# mcp23s17_sample.net
KiCad netlist of a schematic drawn in EAGLE
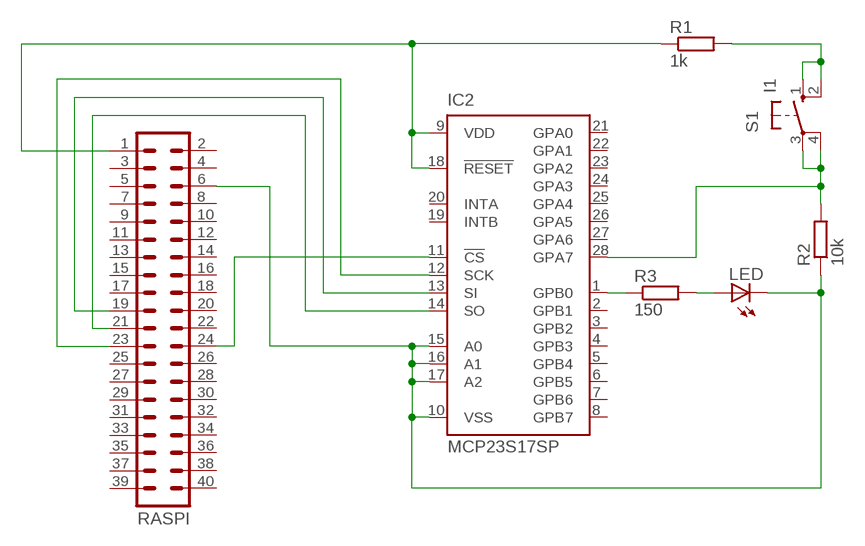
[diagram p0: schematic, sheet 1]

(export (version "E")
  (design (tool "Eeschema 10.0.6"))
  (components
    (comp (ref "IC2")
      (value "MCP23S17SP")
      (footprint "eagle-import:DIL28-3")
      (fields (field (name "MF") "MICROCHIP") (field (name "MPN") "MCP23S17-E/SP"))
      (libsource (lib "eagle-import") (part "MCP23S17SP"))
    )
    (comp (ref "LED")
      (value "LED5MM")
      (footprint "eagle-import:LED5MM")
      (libsource (lib "eagle-import") (part "LED5MM"))
    )
    (comp (ref "R1")
      (value "1k")
      (footprint "eagle-import:0207_10")
      (libsource (lib "eagle-import") (part "R-EU_0207/10"))
    )
    (comp (ref "R2")
      (value "10k")
      (footprint "eagle-import:0207_10")
      (libsource (lib "eagle-import") (part "R-EU_0207/10"))
    )
    (comp (ref "R3")
      (value "150")
      (footprint "eagle-import:0207_10")
      (libsource (lib "eagle-import") (part "R-EU_0207/10"))
    )
    (comp (ref "RASPI")
      (value "ML40")
      (footprint "eagle-import:ML40")
      (libsource (lib "eagle-import") (part "ML40"))
    )
    (comp (ref "S1")
      (value "I1")
      (footprint "eagle-import:B3F-10XX")
      (fields (field (name "MPN") "B3F-1000"))
      (libsource (lib "eagle-import") (part "10-XX"))
    )
  )
  (nets
    (net (code "1") (name "Net-(IC2-A0)") (class "Default")
      (node (ref "IC2") (pin "10") (pinfunction "VSS_10") (pintype "power_in"))
      (node (ref "IC2") (pin "15") (pinfunction "A0_15") (pintype "input"))
      (node (ref "IC2") (pin "16") (pinfunction "A1_16") (pintype "input"))
      (node (ref "IC2") (pin "17") (pinfunction "A2_17") (pintype "input"))
      (node (ref "LED") (pin "K") (pinfunction "C_K") (pintype "passive"))
      (node (ref "R2") (pin "1") (pinfunction "1_1") (pintype "passive"))
      (node (ref "RASPI") (pin "6") (pinfunction "6_6") (pintype "passive"))
    )
    (net (code "2") (name "Net-(IC2-GPA7)") (class "Default")
      (node (ref "IC2") (pin "28") (pinfunction "GPA7_28") (pintype "bidirectional"))
      (node (ref "R2") (pin "2") (pinfunction "2_2") (pintype "passive"))
      (node (ref "S1") (pin "3") (pinfunction "P_3") (pintype "passive"))
      (node (ref "S1") (pin "4") (pinfunction "P1_4") (pintype "passive"))
    )
    (net (code "3") (name "Net-(IC2-GPB0)") (class "Default")
      (node (ref "IC2") (pin "1") (pinfunction "GPB0_1") (pintype "bidirectional"))
      (node (ref "R3") (pin "1") (pinfunction "1_1") (pintype "passive"))
    )
    (net (code "4") (name "Net-(IC2-SCK)") (class "Default")
      (node (ref "IC2") (pin "12") (pinfunction "SCK_12") (pintype "input"))
      (node (ref "RASPI") (pin "23") (pinfunction "23_23") (pintype "passive"))
    )
    (net (code "5") (name "Net-(IC2-SI)") (class "Default")
      (node (ref "IC2") (pin "13") (pinfunction "SI_13") (pintype "input"))
      (node (ref "RASPI") (pin "19") (pinfunction "19_19") (pintype "passive"))
    )
    (net (code "6") (name "Net-(IC2-SO)") (class "Default")
      (node (ref "IC2") (pin "14") (pinfunction "SO_14") (pintype "output"))
      (node (ref "RASPI") (pin "21") (pinfunction "21_21") (pintype "passive"))
    )
    (net (code "7") (name "Net-(IC2-VDD)") (class "Default")
      (node (ref "IC2") (pin "18") (pinfunction "~{RESET}_18") (pintype "input"))
      (node (ref "IC2") (pin "9") (pinfunction "VDD_9") (pintype "power_in"))
      (node (ref "R1") (pin "1") (pinfunction "1_1") (pintype "passive"))
      (node (ref "RASPI") (pin "1") (pinfunction "1_1") (pintype "passive"))
    )
    (net (code "8") (name "Net-(IC2-~{CS})") (class "Default")
      (node (ref "IC2") (pin "11") (pinfunction "~{CS}_11") (pintype "input"))
      (node (ref "RASPI") (pin "24") (pinfunction "24_24") (pintype "passive"))
    )
    (net (code "9") (name "Net-(LED-PadA)") (class "Default")
      (node (ref "LED") (pin "A") (pinfunction "A_A") (pintype "passive"))
      (node (ref "R3") (pin "2") (pinfunction "2_2") (pintype "passive"))
    )
    (net (code "10") (name "Net-(S1-S)") (class "Default")
      (node (ref "R1") (pin "2") (pinfunction "2_2") (pintype "passive"))
      (node (ref "S1") (pin "1") (pinfunction "S_1") (pintype "passive"))
      (node (ref "S1") (pin "2") (pinfunction "S1_2") (pintype "passive"))
    )
    (net (code "11") (name "unconnected-(IC2-GPA0-Pad21)") (class "Default")
      (node (ref "IC2") (pin "21") (pinfunction "GPA0_21") (pintype "bidirectional"))
    )
    (net (code "12") (name "unconnected-(IC2-GPA1-Pad22)") (class "Default")
      (node (ref "IC2") (pin "22") (pinfunction "GPA1_22") (pintype "bidirectional"))
    )
    (net (code "13") (name "unconnected-(IC2-GPA2-Pad23)") (class "Default")
      (node (ref "IC2") (pin "23") (pinfunction "GPA2_23") (pintype "bidirectional"))
    )
    (net (code "14") (name "unconnected-(IC2-GPA3-Pad24)") (class "Default")
      (node (ref "IC2") (pin "24") (pinfunction "GPA3_24") (pintype "bidirectional"))
    )
    (net (code "15") (name "unconnected-(IC2-GPA4-Pad25)") (class "Default")
      (node (ref "IC2") (pin "25") (pinfunction "GPA4_25") (pintype "bidirectional"))
    )
    (net (code "16") (name "unconnected-(IC2-GPA5-Pad26)") (class "Default")
      (node (ref "IC2") (pin "26") (pinfunction "GPA5_26") (pintype "bidirectional"))
    )
    (net (code "17") (name "unconnected-(IC2-GPA6-Pad27)") (class "Default")
      (node (ref "IC2") (pin "27") (pinfunction "GPA6_27") (pintype "bidirectional"))
    )
    (net (code "18") (name "unconnected-(IC2-GPB1-Pad2)") (class "Default")
      (node (ref "IC2") (pin "2") (pinfunction "GPB1_2") (pintype "bidirectional"))
    )
    (net (code "19") (name "unconnected-(IC2-GPB2-Pad3)") (class "Default")
      (node (ref "IC2") (pin "3") (pinfunction "GPB2_3") (pintype "bidirectional"))
    )
    (net (code "20") (name "unconnected-(IC2-GPB3-Pad4)") (class "Default")
      (node (ref "IC2") (pin "4") (pinfunction "GPB3_4") (pintype "bidirectional"))
    )
    (net (code "21") (name "unconnected-(IC2-GPB4-Pad5)") (class "Default")
      (node (ref "IC2") (pin "5") (pinfunction "GPB4_5") (pintype "bidirectional"))
    )
    (net (code "22") (name "unconnected-(IC2-GPB5-Pad6)") (class "Default")
      (node (ref "IC2") (pin "6") (pinfunction "GPB5_6") (pintype "bidirectional"))
    )
    (net (code "23") (name "unconnected-(IC2-GPB6-Pad7)") (class "Default")
      (node (ref "IC2") (pin "7") (pinfunction "GPB6_7") (pintype "bidirectional"))
    )
    (net (code "24") (name "unconnected-(IC2-GPB7-Pad8)") (class "Default")
      (node (ref "IC2") (pin "8") (pinfunction "GPB7_8") (pintype "bidirectional"))
    )
    (net (code "25") (name "unconnected-(IC2-INTA-Pad20)") (class "Default")
      (node (ref "IC2") (pin "20") (pinfunction "INTA_20") (pintype "output"))
    )
    (net (code "26") (name "unconnected-(IC2-INTB-Pad19)") (class "Default")
      (node (ref "IC2") (pin "19") (pinfunction "INTB_19") (pintype "output"))
    )
    (net (code "27") (name "unconnected-(RASPI-Pad2)") (class "Default")
      (node (ref "RASPI") (pin "2") (pinfunction "2_2") (pintype "passive"))
    )
    (net (code "28") (name "unconnected-(RASPI-Pad3)") (class "Default")
      (node (ref "RASPI") (pin "3") (pinfunction "3_3") (pintype "passive"))
    )
    (net (code "29") (name "unconnected-(RASPI-Pad4)") (class "Default")
      (node (ref "RASPI") (pin "4") (pinfunction "4_4") (pintype "passive"))
    )
    (net (code "30") (name "unconnected-(RASPI-Pad5)") (class "Default")
      (node (ref "RASPI") (pin "5") (pinfunction "5_5") (pintype "passive"))
    )
    (net (code "31") (name "unconnected-(RASPI-Pad7)") (class "Default")
      (node (ref "RASPI") (pin "7") (pinfunction "7_7") (pintype "passive"))
    )
    (net (code "32") (name "unconnected-(RASPI-Pad8)") (class "Default")
      (node (ref "RASPI") (pin "8") (pinfunction "8_8") (pintype "passive"))
    )
    (net (code "33") (name "unconnected-(RASPI-Pad9)") (class "Default")
      (node (ref "RASPI") (pin "9") (pinfunction "9_9") (pintype "passive"))
    )
    (net (code "34") (name "unconnected-(RASPI-Pad10)") (class "Default")
      (node (ref "RASPI") (pin "10") (pinfunction "10_10") (pintype "passive"))
    )
    (net (code "35") (name "unconnected-(RASPI-Pad11)") (class "Default")
      (node (ref "RASPI") (pin "11") (pinfunction "11_11") (pintype "passive"))
    )
    (net (code "36") (name "unconnected-(RASPI-Pad12)") (class "Default")
      (node (ref "RASPI") (pin "12") (pinfunction "12_12") (pintype "passive"))
    )
    (net (code "37") (name "unconnected-(RASPI-Pad13)") (class "Default")
      (node (ref "RASPI") (pin "13") (pinfunction "13_13") (pintype "passive"))
    )
    (net (code "38") (name "unconnected-(RASPI-Pad14)") (class "Default")
      (node (ref "RASPI") (pin "14") (pinfunction "14_14") (pintype "passive"))
    )
    (net (code "39") (name "unconnected-(RASPI-Pad15)") (class "Default")
      (node (ref "RASPI") (pin "15") (pinfunction "15_15") (pintype "passive"))
    )
    (net (code "40") (name "unconnected-(RASPI-Pad16)") (class "Default")
      (node (ref "RASPI") (pin "16") (pinfunction "16_16") (pintype "passive"))
    )
    (net (code "41") (name "unconnected-(RASPI-Pad17)") (class "Default")
      (node (ref "RASPI") (pin "17") (pinfunction "17_17") (pintype "passive"))
    )
    (net (code "42") (name "unconnected-(RASPI-Pad18)") (class "Default")
      (node (ref "RASPI") (pin "18") (pinfunction "18_18") (pintype "passive"))
    )
    (net (code "43") (name "unconnected-(RASPI-Pad20)") (class "Default")
      (node (ref "RASPI") (pin "20") (pinfunction "20_20") (pintype "passive"))
    )
    (net (code "44") (name "unconnected-(RASPI-Pad22)") (class "Default")
      (node (ref "RASPI") (pin "22") (pinfunction "22_22") (pintype "passive"))
    )
    (net (code "45") (name "unconnected-(RASPI-Pad25)") (class "Default")
      (node (ref "RASPI") (pin "25") (pinfunction "25_25") (pintype "passive"))
    )
    (net (code "46") (name "unconnected-(RASPI-Pad26)") (class "Default")
      (node (ref "RASPI") (pin "26") (pinfunction "26_26") (pintype "passive"))
    )
    (net (code "47") (name "unconnected-(RASPI-Pad27)") (class "Default")
      (node (ref "RASPI") (pin "27") (pinfunction "27_27") (pintype "passive"))
    )
    (net (code "48") (name "unconnected-(RASPI-Pad28)") (class "Default")
      (node (ref "RASPI") (pin "28") (pinfunction "28_28") (pintype "passive"))
    )
    (net (code "49") (name "unconnected-(RASPI-Pad29)") (class "Default")
      (node (ref "RASPI") (pin "29") (pinfunction "29_29") (pintype "passive"))
    )
    (net (code "50") (name "unconnected-(RASPI-Pad30)") (class "Default")
      (node (ref "RASPI") (pin "30") (pinfunction "30_30") (pintype "passive"))
    )
    (net (code "51") (name "unconnected-(RASPI-Pad31)") (class "Default")
      (node (ref "RASPI") (pin "31") (pinfunction "31_31") (pintype "passive"))
    )
    (net (code "52") (name "unconnected-(RASPI-Pad32)") (class "Default")
      (node (ref "RASPI") (pin "32") (pinfunction "32_32") (pintype "passive"))
    )
    (net (code "53") (name "unconnected-(RASPI-Pad33)") (class "Default")
      (node (ref "RASPI") (pin "33") (pinfunction "33_33") (pintype "passive"))
    )
    (net (code "54") (name "unconnected-(RASPI-Pad34)") (class "Default")
      (node (ref "RASPI") (pin "34") (pinfunction "34_34") (pintype "passive"))
    )
    (net (code "55") (name "unconnected-(RASPI-Pad35)") (class "Default")
      (node (ref "RASPI") (pin "35") (pinfunction "35_35") (pintype "passive"))
    )
    (net (code "56") (name "unconnected-(RASPI-Pad36)") (class "Default")
      (node (ref "RASPI") (pin "36") (pinfunction "36_36") (pintype "passive"))
    )
    (net (code "57") (name "unconnected-(RASPI-Pad37)") (class "Default")
      (node (ref "RASPI") (pin "37") (pinfunction "37_37") (pintype "passive"))
    )
    (net (code "58") (name "unconnected-(RASPI-Pad38)") (class "Default")
      (node (ref "RASPI") (pin "38") (pinfunction "38_38") (pintype "passive"))
    )
    (net (code "59") (name "unconnected-(RASPI-Pad39)") (class "Default")
      (node (ref "RASPI") (pin "39") (pinfunction "39_39") (pintype "passive"))
    )
    (net (code "60") (name "unconnected-(RASPI-Pad40)") (class "Default")
      (node (ref "RASPI") (pin "40") (pinfunction "40_40") (pintype "passive"))
    )
  )
)
